# SH2_-_CAN.net
KiCad netlist of a schematic drawn in Altium Designer
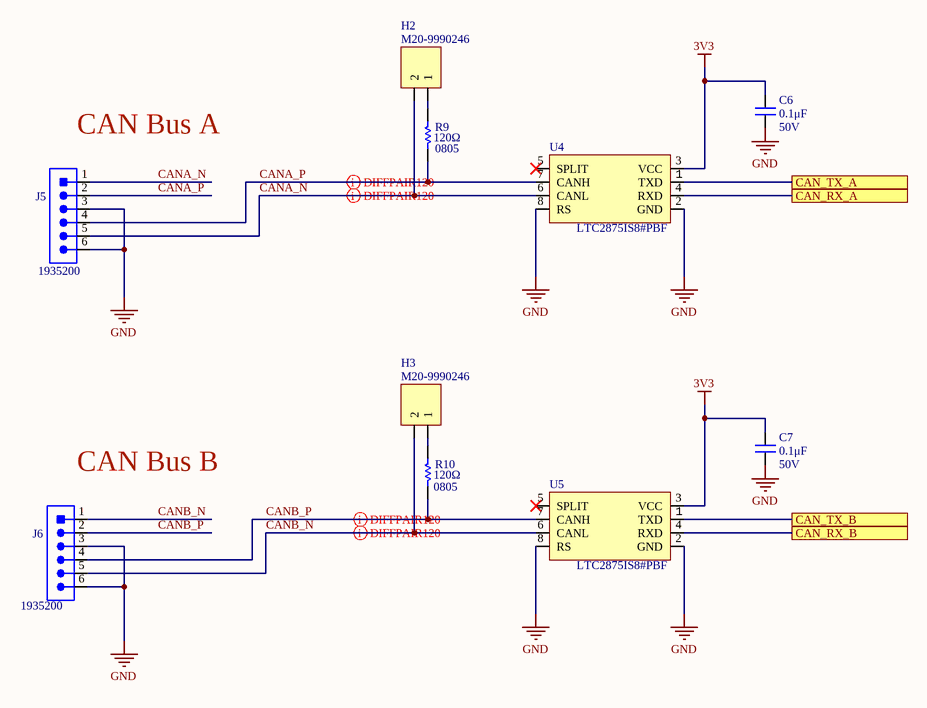
[diagram p0: SH2 - CAN.SchDoc]

(export (version "E")
  (design (tool "Eeschema 10.0.6"))
  (components
    (comp (ref "C6")
      (value "0.1μF")
      (footprint "CAP2012")
      (description "CAP CER 0.1UF 50V X7R 0805")
      (fields
        (field (name "VOLTAGE RATING") "50V")
        (field (name "LCSC PART #") "C49678")
        (field (name "Comment") "CAP_0.1uF_50V_0805")
      )
      (libsource (lib "UWRT_Schematic_Library_2020") (part "CAP_0.1uF_50V_0805"))
    )
    (comp (ref "C7")
      (value "0.1μF")
      (footprint "CAP2012")
      (description "CAP CER 0.1UF 50V X7R 0805")
      (fields
        (field (name "VOLTAGE RATING") "50V")
        (field (name "LCSC PART #") "C49678")
        (field (name "Comment") "CAP_0.1uF_50V_0805")
      )
      (libsource (lib "UWRT_Schematic_Library_2020") (part "CAP_0.1uF_50V_0805"))
    )
    (comp (ref "H2")
      (value "JUMPER")
      (footprint "HDR1X2")
      (description "HEADER 2X1")
      (fields (field (name "MANUFACTURER PART NUMBER 1") "M20-9990246"))
      (libsource (lib "UWRT_Schematic_Library_2020") (part "JUMPER"))
    )
    (comp (ref "H3")
      (value "JUMPER")
      (footprint "HDR1X2")
      (description "HEADER 2X1")
      (fields (field (name "MANUFACTURER PART NUMBER 1") "M20-9990246"))
      (libsource (lib "UWRT_Schematic_Library_2020") (part "JUMPER"))
    )
    (comp (ref "J5")
      (value "CON_6POS_SCREW_TERM")
      (footprint "1935200")
      (description "TERM BLK 6POS SIDE ENTRY 5MM")
      (fields (field (name "MANUFACTURER PART NUMBER 1") "1935200"))
      (libsource (lib "UWRT_Schematic_Library_2020") (part "CON_6POS_SCREW_TERM"))
    )
    (comp (ref "J6")
      (value "CON_6POS_SCREW_TERM")
      (footprint "1935200")
      (description "TERM BLK 6POS SIDE ENTRY 5MM")
      (fields (field (name "MANUFACTURER PART NUMBER 1") "1935200"))
      (libsource (lib "UWRT_Schematic_Library_2020") (part "CON_6POS_SCREW_TERM"))
    )
    (comp (ref "R9")
      (value "120Ω")
      (footprint "RESC0805")
      (description "RES 120 OHM 1% 1/8W 0805")
      (fields
        (field (name "LCSC PART #") "C17437")
        (field (name "PACKAGE/FOOTPRINT") "0805")
        (field (name "Comment") "RES_120Ω_0805_1%")
      )
      (libsource (lib "UWRT_Schematic_Library_2020") (part "RES_120Ω_0805_1%"))
    )
    (comp (ref "R10")
      (value "120Ω")
      (footprint "RESC0805")
      (description "RES 120 OHM 1% 1/8W 0805")
      (fields
        (field (name "LCSC PART #") "C17437")
        (field (name "PACKAGE/FOOTPRINT") "0805")
        (field (name "Comment") "RES_120Ω_0805_1%")
      )
      (libsource (lib "UWRT_Schematic_Library_2020") (part "RES_120Ω_0805_1%"))
    )
    (comp (ref "U4")
      (value "IC_CAN_TRANSCEIVER")
      (footprint "LT-S8_N")
      (description "IC TXRX CAN 4MBPS 8SO")
      (fields
        (field (name "MANUFACTURER PART NUMBER 1") "LTC2875IS8#PBF")
        (field (name "LCSC PART #") "C117076")
      )
      (libsource (lib "UWRT_Schematic_Library_2020") (part "IC_CAN_TRANSCEIVER"))
    )
    (comp (ref "U5")
      (value "IC_CAN_TRANSCEIVER")
      (footprint "LT-S8_N")
      (description "IC TXRX CAN 4MBPS 8SO")
      (fields
        (field (name "MANUFACTURER PART NUMBER 1") "LTC2875IS8#PBF")
        (field (name "LCSC PART #") "C117076")
      )
      (libsource (lib "UWRT_Schematic_Library_2020") (part "IC_CAN_TRANSCEIVER"))
    )
  )
  (nets
    (net (code "1") (name "/CANA_N") (class "Default")
      (node (ref "H2") (pin "2") (pinfunction "2_2") (pintype "passive"))
      (node (ref "J5") (pin "1") (pinfunction "1_1") (pintype "passive"))
      (node (ref "J5") (pin "5") (pinfunction "5_5") (pintype "passive"))
      (node (ref "U4") (pin "6") (pinfunction "CANL_6") (pintype "passive"))
    )
    (net (code "2") (name "/CANA_P") (class "Default")
      (node (ref "J5") (pin "2") (pinfunction "2_2") (pintype "passive"))
      (node (ref "J5") (pin "4") (pinfunction "4_4") (pintype "passive"))
      (node (ref "R9") (pin "1") (pinfunction "1_1") (pintype "passive"))
      (node (ref "U4") (pin "7") (pinfunction "CANH_7") (pintype "passive"))
    )
    (net (code "3") (name "/CANB_N") (class "Default")
      (node (ref "H3") (pin "2") (pinfunction "2_2") (pintype "passive"))
      (node (ref "J6") (pin "1") (pinfunction "1_1") (pintype "passive"))
      (node (ref "J6") (pin "5") (pinfunction "5_5") (pintype "passive"))
      (node (ref "U5") (pin "6") (pinfunction "CANL_6") (pintype "passive"))
    )
    (net (code "4") (name "/CANB_P") (class "Default")
      (node (ref "J6") (pin "2") (pinfunction "2_2") (pintype "passive"))
      (node (ref "J6") (pin "4") (pinfunction "4_4") (pintype "passive"))
      (node (ref "R10") (pin "1") (pinfunction "1_1") (pintype "passive"))
      (node (ref "U5") (pin "7") (pinfunction "CANH_7") (pintype "passive"))
    )
    (net (code "5") (name "/CAN_RX_A") (class "Default")
      (node (ref "U4") (pin "4") (pinfunction "RXD_4") (pintype "passive"))
    )
    (net (code "6") (name "/CAN_RX_B") (class "Default")
      (node (ref "U5") (pin "4") (pinfunction "RXD_4") (pintype "passive"))
    )
    (net (code "7") (name "/CAN_TX_A") (class "Default")
      (node (ref "U4") (pin "1") (pinfunction "TXD_1") (pintype "passive"))
    )
    (net (code "8") (name "/CAN_TX_B") (class "Default")
      (node (ref "U5") (pin "1") (pinfunction "TXD_1") (pintype "passive"))
    )
    (net (code "9") (name "3V3") (class "Default")
      (node (ref "C6") (pin "1") (pinfunction "1_1") (pintype "passive"))
      (node (ref "C7") (pin "1") (pinfunction "1_1") (pintype "passive"))
      (node (ref "U4") (pin "3") (pinfunction "VCC_3") (pintype "passive"))
      (node (ref "U5") (pin "3") (pinfunction "VCC_3") (pintype "passive"))
    )
    (net (code "10") (name "GND") (class "Default")
      (node (ref "C6") (pin "2") (pinfunction "2_2") (pintype "passive"))
      (node (ref "C7") (pin "2") (pinfunction "2_2") (pintype "passive"))
      (node (ref "J5") (pin "3") (pinfunction "3_3") (pintype "passive"))
      (node (ref "J5") (pin "6") (pinfunction "6_6") (pintype "passive"))
      (node (ref "J6") (pin "3") (pinfunction "3_3") (pintype "passive"))
      (node (ref "J6") (pin "6") (pinfunction "6_6") (pintype "passive"))
      (node (ref "U4") (pin "2") (pinfunction "GND_2") (pintype "passive"))
      (node (ref "U4") (pin "8") (pinfunction "RS_8") (pintype "passive"))
      (node (ref "U5") (pin "2") (pinfunction "GND_2") (pintype "passive"))
      (node (ref "U5") (pin "8") (pinfunction "RS_8") (pintype "passive"))
    )
    (net (code "11") (name "Net-(H2-Pad1)") (class "Default")
      (node (ref "H2") (pin "1") (pinfunction "1_1") (pintype "passive"))
      (node (ref "R9") (pin "2") (pinfunction "2_2") (pintype "passive"))
    )
    (net (code "12") (name "Net-(H3-Pad1)") (class "Default")
      (node (ref "H3") (pin "1") (pinfunction "1_1") (pintype "passive"))
      (node (ref "R10") (pin "2") (pinfunction "2_2") (pintype "passive"))
    )
    (net (code "13") (name "unconnected-(U4-SPLIT-Pad5)") (class "Default")
      (node (ref "U4") (pin "5") (pinfunction "SPLIT_5") (pintype "passive+no_connect"))
    )
    (net (code "14") (name "unconnected-(U5-SPLIT-Pad5)") (class "Default")
      (node (ref "U5") (pin "5") (pinfunction "SPLIT_5") (pintype "passive+no_connect"))
    )
  )
)
